# 32.net
KiCad netlist of a schematic drawn in Altium Designer
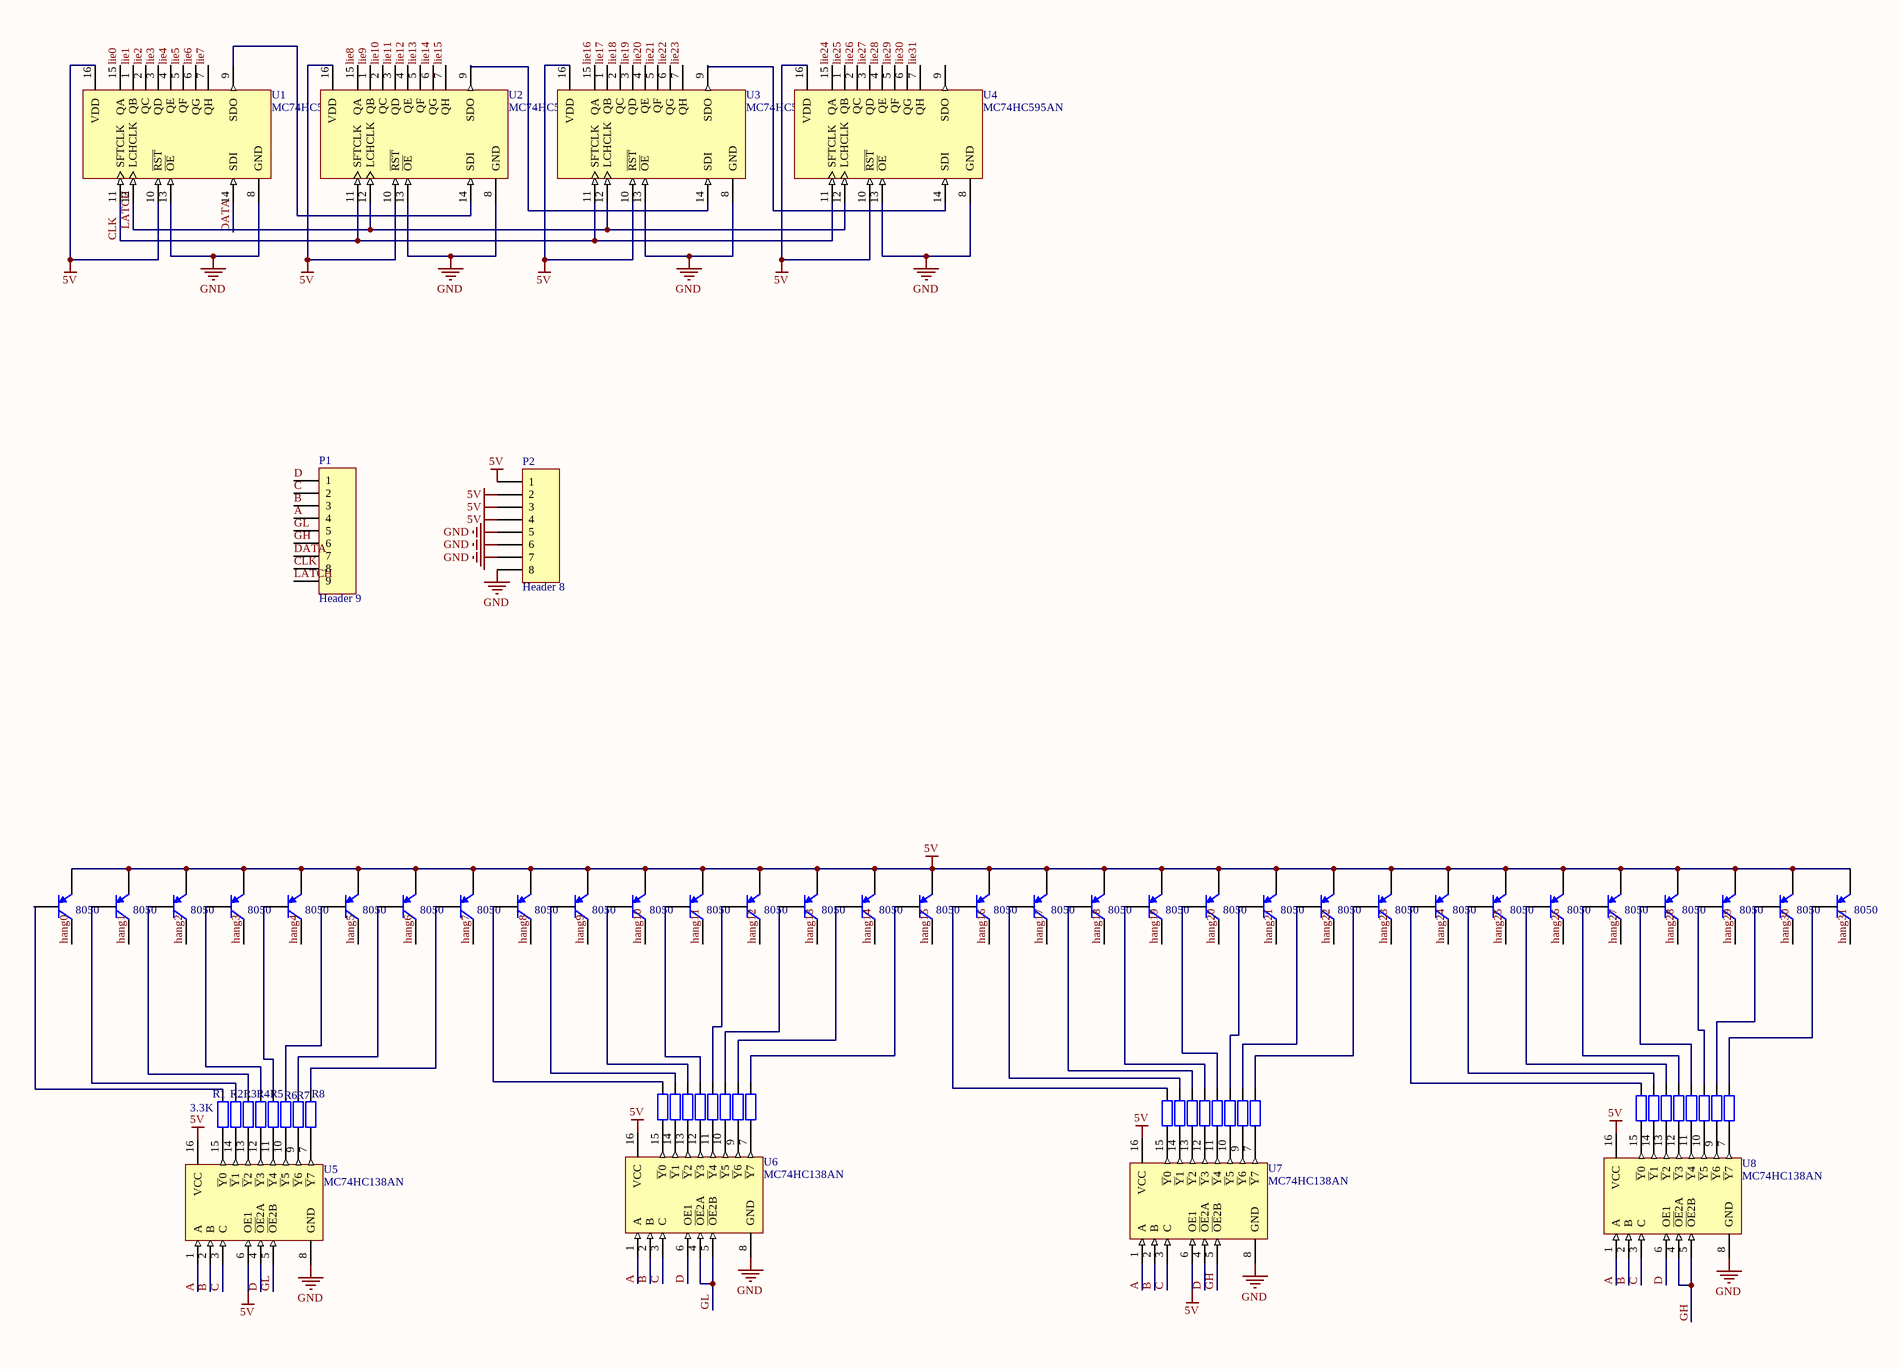
[diagram p0: 32点阵.SchDoc, left]
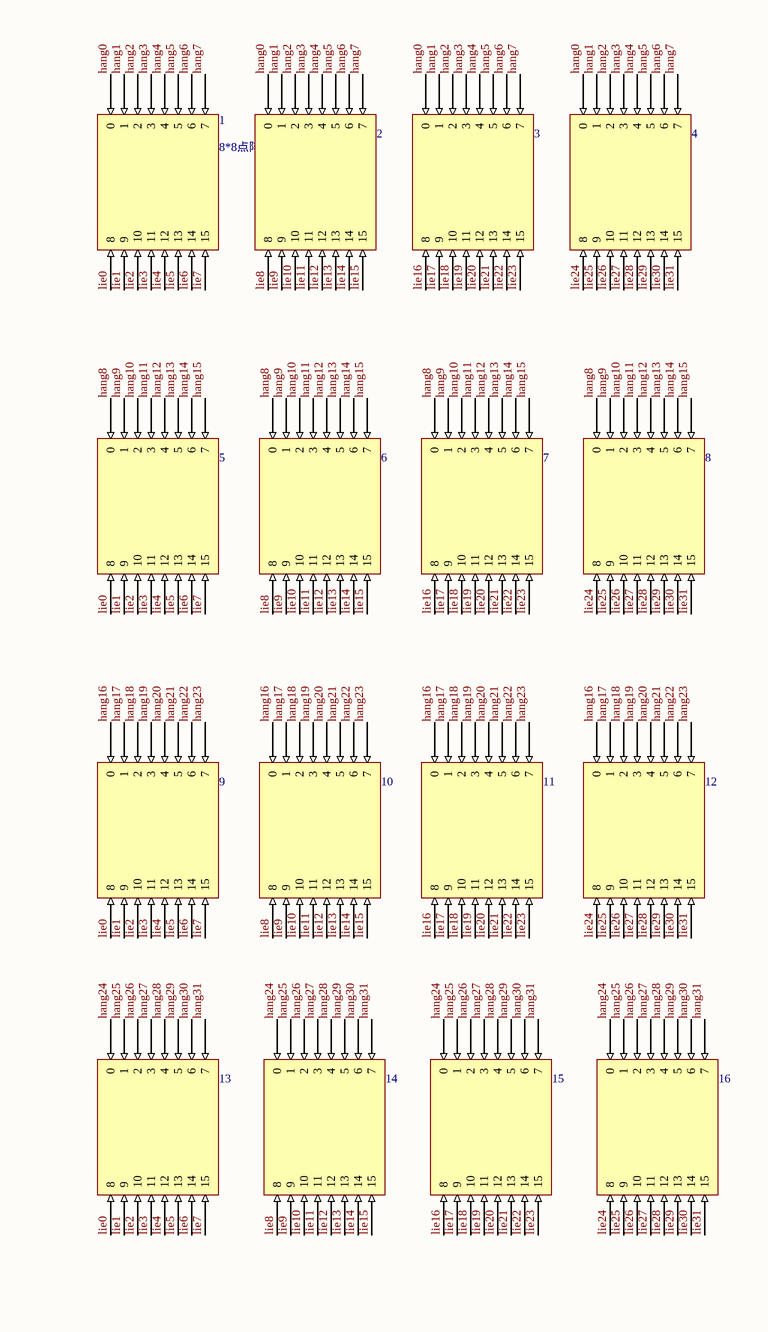
[diagram p1: 32点阵.SchDoc, right]

(export (version "E")
  (design (tool "Eeschema 10.0.6"))
  (components
    (comp (ref "1")
      (value "8乘8点阵")
      (footprint "32点阵:PCBComponent_1 - duplicate")
      (fields (field (name "8*8ΜÃÕÓ") "上面行，下面列"))
      (libsource (lib "88点阵") (part "8乘8点阵"))
    )
    (comp (ref "2")
      (value "8乘8点阵")
      (footprint "32点阵:PCBComponent_1 - duplicate")
      (libsource (lib "88点阵") (part "8乘8点阵"))
    )
    (comp (ref "3")
      (value "8乘8点阵")
      (footprint "32点阵:PCBComponent_1 - duplicate")
      (libsource (lib "88点阵") (part "8乘8点阵"))
    )
    (comp (ref "4")
      (value "8乘8点阵")
      (footprint "32点阵:PCBComponent_1 - duplicate")
      (libsource (lib "88点阵") (part "8乘8点阵"))
    )
    (comp (ref "5")
      (value "8乘8点阵")
      (footprint "32点阵:PCBComponent_1 - duplicate")
      (libsource (lib "88点阵") (part "8乘8点阵"))
    )
    (comp (ref "6")
      (value "8乘8点阵")
      (footprint "32点阵:PCBComponent_1 - duplicate")
      (libsource (lib "88点阵") (part "8乘8点阵"))
    )
    (comp (ref "7")
      (value "8乘8点阵")
      (footprint "32点阵:PCBComponent_1 - duplicate")
      (libsource (lib "88点阵") (part "8乘8点阵"))
    )
    (comp (ref "8")
      (value "8乘8点阵")
      (footprint "32点阵:PCBComponent_1 - duplicate")
      (libsource (lib "88点阵") (part "8乘8点阵"))
    )
    (comp (ref "9")
      (value "8乘8点阵")
      (footprint "32点阵:PCBComponent_1 - duplicate")
      (libsource (lib "88点阵") (part "8乘8点阵"))
    )
    (comp (ref "10")
      (value "8乘8点阵")
      (footprint "32点阵:PCBComponent_1 - duplicate")
      (libsource (lib "88点阵") (part "8乘8点阵"))
    )
    (comp (ref "11")
      (value "8乘8点阵")
      (footprint "32点阵:PCBComponent_1 - duplicate")
      (libsource (lib "88点阵") (part "8乘8点阵"))
    )
    (comp (ref "12")
      (value "8乘8点阵")
      (footprint "32点阵:PCBComponent_1 - duplicate")
      (libsource (lib "88点阵") (part "8乘8点阵"))
    )
    (comp (ref "13")
      (value "8乘8点阵")
      (footprint "32点阵:PCBComponent_1 - duplicate")
      (libsource (lib "88点阵") (part "8乘8点阵"))
    )
    (comp (ref "14")
      (value "8乘8点阵")
      (footprint "32点阵:PCBComponent_1 - duplicate")
      (libsource (lib "88点阵") (part "8乘8点阵"))
    )
    (comp (ref "15")
      (value "8乘8点阵")
      (footprint "32点阵:PCBComponent_1 - duplicate")
      (libsource (lib "88点阵") (part "8乘8点阵"))
    )
    (comp (ref "16")
      (value "8乘8点阵")
      (footprint "32点阵:PCBComponent_1 - duplicate")
      (libsource (lib "88点阵") (part "8乘8点阵"))
    )
    (comp (ref "P1")
      (value "Header 9")
      (footprint "HDR1X9")
      (description "Header, 9-Pin")
      (fields (field (name "PUBLISHER") "Altium Limited"))
      (libsource (lib "Miscellaneous Connectors") (part "Header 9"))
    )
    (comp (ref "P2")
      (value "Header 8")
      (footprint "HDR1X8")
      (description "Header, 8-Pin")
      (fields (field (name "PUBLISHER") "Altium Limited"))
      (libsource (lib "Miscellaneous Connectors") (part "Header 8"))
    )
    (comp (ref "Q1")
      (value "8050")
      (footprint "TO-92A")
      (description "PNP General Purpose Amplifier")
      (fields (field (name "PUBLISHER") "Altium Limited"))
      (libsource (lib "Miscellaneous Devices") (part "2N3906"))
    )
    (comp (ref "Q2")
      (value "8050")
      (footprint "TO-92A")
      (description "PNP General Purpose Amplifier")
      (fields (field (name "PUBLISHER") "Altium Limited"))
      (libsource (lib "Miscellaneous Devices") (part "2N3906"))
    )
    (comp (ref "Q3")
      (value "8050")
      (footprint "TO-92A")
      (description "PNP General Purpose Amplifier")
      (fields (field (name "PUBLISHER") "Altium Limited"))
      (libsource (lib "Miscellaneous Devices") (part "2N3906"))
    )
    (comp (ref "Q4")
      (value "8050")
      (footprint "TO-92A")
      (description "PNP General Purpose Amplifier")
      (fields (field (name "PUBLISHER") "Altium Limited"))
      (libsource (lib "Miscellaneous Devices") (part "2N3906"))
    )
    (comp (ref "Q5")
      (value "8050")
      (footprint "TO-92A")
      (description "PNP General Purpose Amplifier")
      (fields (field (name "PUBLISHER") "Altium Limited"))
      (libsource (lib "Miscellaneous Devices") (part "2N3906"))
    )
    (comp (ref "Q6")
      (value "8050")
      (footprint "TO-92A")
      (description "PNP General Purpose Amplifier")
      (fields (field (name "PUBLISHER") "Altium Limited"))
      (libsource (lib "Miscellaneous Devices") (part "2N3906"))
    )
    (comp (ref "Q7")
      (value "8050")
      (footprint "TO-92A")
      (description "PNP General Purpose Amplifier")
      (fields (field (name "PUBLISHER") "Altium Limited"))
      (libsource (lib "Miscellaneous Devices") (part "2N3906"))
    )
    (comp (ref "Q8")
      (value "8050")
      (footprint "TO-92A")
      (description "PNP General Purpose Amplifier")
      (fields (field (name "PUBLISHER") "Altium Limited"))
      (libsource (lib "Miscellaneous Devices") (part "2N3906"))
    )
    (comp (ref "Q9")
      (value "8050")
      (footprint "TO-92A")
      (description "PNP General Purpose Amplifier")
      (fields (field (name "PUBLISHER") "Altium Limited"))
      (libsource (lib "Miscellaneous Devices") (part "2N3906"))
    )
    (comp (ref "Q10")
      (value "8050")
      (footprint "TO-92A")
      (description "PNP General Purpose Amplifier")
      (fields (field (name "PUBLISHER") "Altium Limited"))
      (libsource (lib "Miscellaneous Devices") (part "2N3906"))
    )
    (comp (ref "Q11")
      (value "8050")
      (footprint "TO-92A")
      (description "PNP General Purpose Amplifier")
      (fields (field (name "PUBLISHER") "Altium Limited"))
      (libsource (lib "Miscellaneous Devices") (part "2N3906"))
    )
    (comp (ref "Q12")
      (value "8050")
      (footprint "TO-92A")
      (description "PNP General Purpose Amplifier")
      (fields (field (name "PUBLISHER") "Altium Limited"))
      (libsource (lib "Miscellaneous Devices") (part "2N3906"))
    )
    (comp (ref "Q13")
      (value "8050")
      (footprint "TO-92A")
      (description "PNP General Purpose Amplifier")
      (fields (field (name "PUBLISHER") "Altium Limited"))
      (libsource (lib "Miscellaneous Devices") (part "2N3906"))
    )
    (comp (ref "Q14")
      (value "8050")
      (footprint "TO-92A")
      (description "PNP General Purpose Amplifier")
      (fields (field (name "PUBLISHER") "Altium Limited"))
      (libsource (lib "Miscellaneous Devices") (part "2N3906"))
    )
    (comp (ref "Q15")
      (value "8050")
      (footprint "TO-92A")
      (description "PNP General Purpose Amplifier")
      (fields (field (name "PUBLISHER") "Altium Limited"))
      (libsource (lib "Miscellaneous Devices") (part "2N3906"))
    )
    (comp (ref "Q16")
      (value "8050")
      (footprint "TO-92A")
      (description "PNP General Purpose Amplifier")
      (fields (field (name "PUBLISHER") "Altium Limited"))
      (libsource (lib "Miscellaneous Devices") (part "2N3906"))
    )
    (comp (ref "Q17")
      (value "8050")
      (footprint "TO-92A")
      (description "PNP General Purpose Amplifier")
      (fields (field (name "PUBLISHER") "Altium Limited"))
      (libsource (lib "Miscellaneous Devices") (part "2N3906"))
    )
    (comp (ref "Q18")
      (value "8050")
      (footprint "TO-92A")
      (description "PNP General Purpose Amplifier")
      (fields (field (name "PUBLISHER") "Altium Limited"))
      (libsource (lib "Miscellaneous Devices") (part "2N3906"))
    )
    (comp (ref "Q19")
      (value "8050")
      (footprint "TO-92A")
      (description "PNP General Purpose Amplifier")
      (fields (field (name "PUBLISHER") "Altium Limited"))
      (libsource (lib "Miscellaneous Devices") (part "2N3906"))
    )
    (comp (ref "Q20")
      (value "8050")
      (footprint "TO-92A")
      (description "PNP General Purpose Amplifier")
      (fields (field (name "PUBLISHER") "Altium Limited"))
      (libsource (lib "Miscellaneous Devices") (part "2N3906"))
    )
    (comp (ref "Q21")
      (value "8050")
      (footprint "TO-92A")
      (description "PNP General Purpose Amplifier")
      (fields (field (name "PUBLISHER") "Altium Limited"))
      (libsource (lib "Miscellaneous Devices") (part "2N3906"))
    )
    (comp (ref "Q22")
      (value "8050")
      (footprint "TO-92A")
      (description "PNP General Purpose Amplifier")
      (fields (field (name "PUBLISHER") "Altium Limited"))
      (libsource (lib "Miscellaneous Devices") (part "2N3906"))
    )
    (comp (ref "Q23")
      (value "8050")
      (footprint "TO-92A")
      (description "PNP General Purpose Amplifier")
      (fields (field (name "PUBLISHER") "Altium Limited"))
      (libsource (lib "Miscellaneous Devices") (part "2N3906"))
    )
    (comp (ref "Q24")
      (value "8050")
      (footprint "TO-92A")
      (description "PNP General Purpose Amplifier")
      (fields (field (name "PUBLISHER") "Altium Limited"))
      (libsource (lib "Miscellaneous Devices") (part "2N3906"))
    )
    (comp (ref "Q25")
      (value "8050")
      (footprint "TO-92A")
      (description "PNP General Purpose Amplifier")
      (fields (field (name "PUBLISHER") "Altium Limited"))
      (libsource (lib "Miscellaneous Devices") (part "2N3906"))
    )
    (comp (ref "Q26")
      (value "8050")
      (footprint "TO-92A")
      (description "PNP General Purpose Amplifier")
      (fields (field (name "PUBLISHER") "Altium Limited"))
      (libsource (lib "Miscellaneous Devices") (part "2N3906"))
    )
    (comp (ref "Q27")
      (value "8050")
      (footprint "TO-92A")
      (description "PNP General Purpose Amplifier")
      (fields (field (name "PUBLISHER") "Altium Limited"))
      (libsource (lib "Miscellaneous Devices") (part "2N3906"))
    )
    (comp (ref "Q28")
      (value "8050")
      (footprint "TO-92A")
      (description "PNP General Purpose Amplifier")
      (fields (field (name "PUBLISHER") "Altium Limited"))
      (libsource (lib "Miscellaneous Devices") (part "2N3906"))
    )
    (comp (ref "Q29")
      (value "8050")
      (footprint "TO-92A")
      (description "PNP General Purpose Amplifier")
      (fields (field (name "PUBLISHER") "Altium Limited"))
      (libsource (lib "Miscellaneous Devices") (part "2N3906"))
    )
    (comp (ref "Q30")
      (value "8050")
      (footprint "TO-92A")
      (description "PNP General Purpose Amplifier")
      (fields (field (name "PUBLISHER") "Altium Limited"))
      (libsource (lib "Miscellaneous Devices") (part "2N3906"))
    )
    (comp (ref "Q31")
      (value "8050")
      (footprint "TO-92A")
      (description "PNP General Purpose Amplifier")
      (fields (field (name "PUBLISHER") "Altium Limited"))
      (libsource (lib "Miscellaneous Devices") (part "2N3906"))
    )
    (comp (ref "Q32")
      (value "8050")
      (footprint "TO-92A")
      (description "PNP General Purpose Amplifier")
      (fields (field (name "PUBLISHER") "Altium Limited"))
      (libsource (lib "Miscellaneous Devices") (part "2N3906"))
    )
    (comp (ref "R1")
      (value "3.3K")
      (footprint "AXIAL-0.4")
      (description "Resistor")
      (fields (field (name "Comment") "Res2") (field (name "PUBLISHER") "Altium Limited"))
      (libsource (lib "Miscellaneous Devices") (part "Res2"))
    )
    (comp (ref "R2")
      (value "Res2")
      (footprint "AXIAL-0.4")
      (description "Resistor")
      (fields (field (name "PUBLISHER") "Altium Limited"))
      (libsource (lib "Miscellaneous Devices") (part "Res2"))
    )
    (comp (ref "R3")
      (value "Res2")
      (footprint "AXIAL-0.4")
      (description "Resistor")
      (fields (field (name "PUBLISHER") "Altium Limited"))
      (libsource (lib "Miscellaneous Devices") (part "Res2"))
    )
    (comp (ref "R4")
      (value "Res2")
      (footprint "AXIAL-0.4")
      (description "Resistor")
      (fields (field (name "PUBLISHER") "Altium Limited"))
      (libsource (lib "Miscellaneous Devices") (part "Res2"))
    )
    (comp (ref "R5")
      (value "Res2")
      (footprint "AXIAL-0.4")
      (description "Resistor")
      (fields (field (name "PUBLISHER") "Altium Limited"))
      (libsource (lib "Miscellaneous Devices") (part "Res2"))
    )
    (comp (ref "R6")
      (value "Res2")
      (footprint "AXIAL-0.4")
      (description "Resistor")
      (fields (field (name "PUBLISHER") "Altium Limited"))
      (libsource (lib "Miscellaneous Devices") (part "Res2"))
    )
    (comp (ref "R7")
      (value "Res2")
      (footprint "AXIAL-0.4")
      (description "Resistor")
      (fields (field (name "PUBLISHER") "Altium Limited"))
      (libsource (lib "Miscellaneous Devices") (part "Res2"))
    )
    (comp (ref "R8")
      (value "Res2")
      (footprint "AXIAL-0.4")
      (description "Resistor")
      (fields (field (name "PUBLISHER") "Altium Limited"))
      (libsource (lib "Miscellaneous Devices") (part "Res2"))
    )
    (comp (ref "R9")
      (value "Res2")
      (footprint "AXIAL-0.4")
      (description "Resistor")
      (fields (field (name "PUBLISHER") "Altium Limited"))
      (libsource (lib "Miscellaneous Devices") (part "Res2"))
    )
    (comp (ref "R10")
      (value "Res2")
      (footprint "AXIAL-0.4")
      (description "Resistor")
      (fields (field (name "PUBLISHER") "Altium Limited"))
      (libsource (lib "Miscellaneous Devices") (part "Res2"))
    )
    (comp (ref "R11")
      (value "Res2")
      (footprint "AXIAL-0.4")
      (description "Resistor")
      (fields (field (name "PUBLISHER") "Altium Limited"))
      (libsource (lib "Miscellaneous Devices") (part "Res2"))
    )
    (comp (ref "R12")
      (value "Res2")
      (footprint "AXIAL-0.4")
      (description "Resistor")
      (fields (field (name "PUBLISHER") "Altium Limited"))
      (libsource (lib "Miscellaneous Devices") (part "Res2"))
    )
    (comp (ref "R13")
      (value "Res2")
      (footprint "AXIAL-0.4")
      (description "Resistor")
      (fields (field (name "PUBLISHER") "Altium Limited"))
      (libsource (lib "Miscellaneous Devices") (part "Res2"))
    )
    (comp (ref "R14")
      (value "Res2")
      (footprint "AXIAL-0.4")
      (description "Resistor")
      (fields (field (name "PUBLISHER") "Altium Limited"))
      (libsource (lib "Miscellaneous Devices") (part "Res2"))
    )
    (comp (ref "R15")
      (value "Res2")
      (footprint "AXIAL-0.4")
      (description "Resistor")
      (fields (field (name "PUBLISHER") "Altium Limited"))
      (libsource (lib "Miscellaneous Devices") (part "Res2"))
    )
    (comp (ref "R16")
      (value "Res2")
      (footprint "AXIAL-0.4")
      (description "Resistor")
      (fields (field (name "PUBLISHER") "Altium Limited"))
      (libsource (lib "Miscellaneous Devices") (part "Res2"))
    )
    (comp (ref "R17")
      (value "Res2")
      (footprint "AXIAL-0.4")
      (description "Resistor")
      (fields (field (name "PUBLISHER") "Altium Limited"))
      (libsource (lib "Miscellaneous Devices") (part "Res2"))
    )
    (comp (ref "R18")
      (value "Res2")
      (footprint "AXIAL-0.4")
      (description "Resistor")
      (fields (field (name "PUBLISHER") "Altium Limited"))
      (libsource (lib "Miscellaneous Devices") (part "Res2"))
    )
    (comp (ref "R19")
      (value "Res2")
      (footprint "AXIAL-0.4")
      (description "Resistor")
      (fields (field (name "PUBLISHER") "Altium Limited"))
      (libsource (lib "Miscellaneous Devices") (part "Res2"))
    )
    (comp (ref "R20")
      (value "Res2")
      (footprint "AXIAL-0.4")
      (description "Resistor")
      (fields (field (name "PUBLISHER") "Altium Limited"))
      (libsource (lib "Miscellaneous Devices") (part "Res2"))
    )
    (comp (ref "R21")
      (value "Res2")
      (footprint "AXIAL-0.4")
      (description "Resistor")
      (fields (field (name "PUBLISHER") "Altium Limited"))
      (libsource (lib "Miscellaneous Devices") (part "Res2"))
    )
    (comp (ref "R22")
      (value "Res2")
      (footprint "AXIAL-0.4")
      (description "Resistor")
      (fields (field (name "PUBLISHER") "Altium Limited"))
      (libsource (lib "Miscellaneous Devices") (part "Res2"))
    )
    (comp (ref "R23")
      (value "Res2")
      (footprint "AXIAL-0.4")
      (description "Resistor")
      (fields (field (name "PUBLISHER") "Altium Limited"))
      (libsource (lib "Miscellaneous Devices") (part "Res2"))
    )
    (comp (ref "R24")
      (value "Res2")
      (footprint "AXIAL-0.4")
      (description "Resistor")
      (fields (field (name "PUBLISHER") "Altium Limited"))
      (libsource (lib "Miscellaneous Devices") (part "Res2"))
    )
    (comp (ref "R25")
      (value "Res2")
      (footprint "AXIAL-0.4")
      (description "Resistor")
      (fields (field (name "PUBLISHER") "Altium Limited"))
      (libsource (lib "Miscellaneous Devices") (part "Res2"))
    )
    (comp (ref "R26")
      (value "Res2")
      (footprint "AXIAL-0.4")
      (description "Resistor")
      (fields (field (name "PUBLISHER") "Altium Limited"))
      (libsource (lib "Miscellaneous Devices") (part "Res2"))
    )
    (comp (ref "R27")
      (value "Res2")
      (footprint "AXIAL-0.4")
      (description "Resistor")
      (fields (field (name "PUBLISHER") "Altium Limited"))
      (libsource (lib "Miscellaneous Devices") (part "Res2"))
    )
    (comp (ref "R28")
      (value "Res2")
      (footprint "AXIAL-0.4")
      (description "Resistor")
      (fields (field (name "PUBLISHER") "Altium Limited"))
      (libsource (lib "Miscellaneous Devices") (part "Res2"))
    )
    (comp (ref "R29")
      (value "Res2")
      (footprint "AXIAL-0.4")
      (description "Resistor")
      (fields (field (name "PUBLISHER") "Altium Limited"))
      (libsource (lib "Miscellaneous Devices") (part "Res2"))
    )
    (comp (ref "R30")
      (value "Res2")
      (footprint "AXIAL-0.4")
      (description "Resistor")
      (fields (field (name "PUBLISHER") "Altium Limited"))
      (libsource (lib "Miscellaneous Devices") (part "Res2"))
    )
    (comp (ref "R31")
      (value "Res2")
      (footprint "AXIAL-0.4")
      (description "Resistor")
      (fields (field (name "PUBLISHER") "Altium Limited"))
      (libsource (lib "Miscellaneous Devices") (part "Res2"))
    )
    (comp (ref "R32")
      (value "Res2")
      (footprint "AXIAL-0.4")
      (description "Resistor")
      (fields (field (name "PUBLISHER") "Altium Limited"))
      (libsource (lib "Miscellaneous Devices") (part "Res2"))
    )
    (comp (ref "U1")
      (value "MC74HC595AN")
      (footprint "648-08")
      (description "8-Bit Serial-Input/Serial or Prallel-Output Shift Register with Latched 3-State Outputs")
      (fields (field (name "PUBLISHER") "Altium Limited"))
      (libsource (lib "ON Semi Logic Register") (part "MC74HC595AN"))
    )
    (comp (ref "U2")
      (value "MC74HC595AN")
      (footprint "648-08")
      (description "8-Bit Serial-Input/Serial or Prallel-Output Shift Register with Latched 3-State Outputs")
      (fields (field (name "PUBLISHER") "Altium Limited"))
      (libsource (lib "ON Semi Logic Register") (part "MC74HC595AN"))
    )
    (comp (ref "U3")
      (value "MC74HC595AN")
      (footprint "648-08")
      (description "8-Bit Serial-Input/Serial or Prallel-Output Shift Register with Latched 3-State Outputs")
      (fields (field (name "PUBLISHER") "Altium Limited"))
      (libsource (lib "ON Semi Logic Register") (part "MC74HC595AN"))
    )
    (comp (ref "U4")
      (value "MC74HC595AN")
      (footprint "648-08")
      (description "8-Bit Serial-Input/Serial or Prallel-Output Shift Register with Latched 3-State Outputs")
      (fields (field (name "PUBLISHER") "Altium Limited"))
      (libsource (lib "ON Semi Logic Register") (part "MC74HC595AN"))
    )
    (comp (ref "U5")
      (value "MC74HC138AN")
      (footprint "648-08")
      (description "1-of-8 Decoder/Demultiplexer")
      (fields (field (name "PUBLISHER") "Altium Limited"))
      (libsource (lib "ON Semi Logic Decoder Demux") (part "MC74HC138AN"))
    )
    (comp (ref "U6")
      (value "MC74HC138AN")
      (footprint "648-08")
      (description "1-of-8 Decoder/Demultiplexer")
      (fields (field (name "PUBLISHER") "Altium Limited"))
      (libsource (lib "ON Semi Logic Decoder Demux") (part "MC74HC138AN"))
    )
    (comp (ref "U7")
      (value "MC74HC138AN")
      (footprint "648-08")
      (description "1-of-8 Decoder/Demultiplexer")
      (fields (field (name "PUBLISHER") "Altium Limited"))
      (libsource (lib "ON Semi Logic Decoder Demux") (part "MC74HC138AN"))
    )
    (comp (ref "U8")
      (value "MC74HC138AN")
      (footprint "648-08")
      (description "1-of-8 Decoder/Demultiplexer")
      (fields (field (name "PUBLISHER") "Altium Limited"))
      (libsource (lib "ON Semi Logic Decoder Demux") (part "MC74HC138AN"))
    )
  )
  (nets
    (net (code "1") (name "/A") (class "Default")
      (node (ref "P1") (pin "4") (pinfunction "4_4") (pintype "passive"))
      (node (ref "U5") (pin "1") (pinfunction "A_1") (pintype "input"))
      (node (ref "U6") (pin "1") (pinfunction "A_1") (pintype "input"))
      (node (ref "U7") (pin "1") (pinfunction "A_1") (pintype "input"))
      (node (ref "U8") (pin "1") (pinfunction "A_1") (pintype "input"))
    )
    (net (code "2") (name "/B") (class "Default")
      (node (ref "P1") (pin "3") (pinfunction "3_3") (pintype "passive"))
      (node (ref "U5") (pin "2") (pinfunction "B_2") (pintype "input"))
      (node (ref "U6") (pin "2") (pinfunction "B_2") (pintype "input"))
      (node (ref "U7") (pin "2") (pinfunction "B_2") (pintype "input"))
      (node (ref "U8") (pin "2") (pinfunction "B_2") (pintype "input"))
    )
    (net (code "3") (name "/C") (class "Default")
      (node (ref "P1") (pin "2") (pinfunction "2_2") (pintype "passive"))
      (node (ref "U5") (pin "3") (pinfunction "C_3") (pintype "input"))
      (node (ref "U6") (pin "3") (pinfunction "C_3") (pintype "input"))
      (node (ref "U7") (pin "3") (pinfunction "C_3") (pintype "input"))
      (node (ref "U8") (pin "3") (pinfunction "C_3") (pintype "input"))
    )
    (net (code "4") (name "/CLK") (class "Default")
      (node (ref "P1") (pin "8") (pinfunction "8_8") (pintype "passive"))
      (node (ref "U1") (pin "11") (pinfunction "SFTCLK_11") (pintype "input"))
      (node (ref "U2") (pin "11") (pinfunction "SFTCLK_11") (pintype "input"))
      (node (ref "U3") (pin "11") (pinfunction "SFTCLK_11") (pintype "input"))
      (node (ref "U4") (pin "11") (pinfunction "SFTCLK_11") (pintype "input"))
    )
    (net (code "5") (name "/D") (class "Default")
      (node (ref "P1") (pin "1") (pinfunction "1_1") (pintype "passive"))
      (node (ref "U5") (pin "4") (pinfunction "~{OE}2A_4") (pintype "input"))
      (node (ref "U6") (pin "6") (pinfunction "OE1_6") (pintype "input"))
      (node (ref "U7") (pin "4") (pinfunction "~{OE}2A_4") (pintype "input"))
      (node (ref "U8") (pin "6") (pinfunction "OE1_6") (pintype "input"))
    )
    (net (code "6") (name "/DATA") (class "Default")
      (node (ref "P1") (pin "7") (pinfunction "7_7") (pintype "passive"))
      (node (ref "U1") (pin "14") (pinfunction "SDI_14") (pintype "input"))
    )
    (net (code "7") (name "/GH") (class "Default")
      (node (ref "P1") (pin "6") (pinfunction "6_6") (pintype "passive"))
      (node (ref "U7") (pin "5") (pinfunction "~{OE}2B_5") (pintype "input"))
      (node (ref "U8") (pin "4") (pinfunction "~{OE}2A_4") (pintype "input"))
      (node (ref "U8") (pin "5") (pinfunction "~{OE}2B_5") (pintype "input"))
    )
    (net (code "8") (name "/GL") (class "Default")
      (node (ref "P1") (pin "5") (pinfunction "5_5") (pintype "passive"))
      (node (ref "U5") (pin "5") (pinfunction "~{OE}2B_5") (pintype "input"))
      (node (ref "U6") (pin "4") (pinfunction "~{OE}2A_4") (pintype "input"))
      (node (ref "U6") (pin "5") (pinfunction "~{OE}2B_5") (pintype "input"))
    )
    (net (code "9") (name "/LATCH") (class "Default")
      (node (ref "P1") (pin "9") (pinfunction "9_9") (pintype "passive"))
      (node (ref "U1") (pin "12") (pinfunction "LCHCLK_12") (pintype "input"))
      (node (ref "U2") (pin "12") (pinfunction "LCHCLK_12") (pintype "input"))
      (node (ref "U3") (pin "12") (pinfunction "LCHCLK_12") (pintype "input"))
      (node (ref "U4") (pin "12") (pinfunction "LCHCLK_12") (pintype "input"))
    )
    (net (code "10") (name "/hang0") (class "Default")
      (node (ref "1") (pin "0") (pinfunction "0_0") (pintype "input"))
      (node (ref "2") (pin "0") (pinfunction "0_0") (pintype "input"))
      (node (ref "3") (pin "0") (pinfunction "0_0") (pintype "input"))
      (node (ref "4") (pin "0") (pinfunction "0_0") (pintype "input"))
      (node (ref "Q1") (pin "3") (pinfunction "C_3") (pintype "passive"))
    )
    (net (code "11") (name "/hang1") (class "Default")
      (node (ref "1") (pin "1") (pinfunction "1_1") (pintype "input"))
      (node (ref "2") (pin "1") (pinfunction "1_1") (pintype "input"))
      (node (ref "3") (pin "1") (pinfunction "1_1") (pintype "input"))
      (node (ref "4") (pin "1") (pinfunction "1_1") (pintype "input"))
      (node (ref "Q2") (pin "3") (pinfunction "C_3") (pintype "passive"))
    )
    (net (code "12") (name "/hang2") (class "Default")
      (node (ref "1") (pin "2") (pinfunction "2_2") (pintype "input"))
      (node (ref "2") (pin "2") (pinfunction "2_2") (pintype "input"))
      (node (ref "3") (pin "2") (pinfunction "2_2") (pintype "input"))
      (node (ref "4") (pin "2") (pinfunction "2_2") (pintype "input"))
      (node (ref "Q3") (pin "3") (pinfunction "C_3") (pintype "passive"))
    )
    (net (code "13") (name "/hang3") (class "Default")
      (node (ref "1") (pin "3") (pinfunction "3_3") (pintype "input"))
      (node (ref "2") (pin "3") (pinfunction "3_3") (pintype "input"))
      (node (ref "3") (pin "3") (pinfunction "3_3") (pintype "input"))
      (node (ref "4") (pin "3") (pinfunction "3_3") (pintype "input"))
      (node (ref "Q4") (pin "3") (pinfunction "C_3") (pintype "passive"))
    )
    (net (code "14") (name "/hang4") (class "Default")
      (node (ref "1") (pin "4") (pinfunction "4_4") (pintype "input"))
      (node (ref "2") (pin "4") (pinfunction "4_4") (pintype "input"))
      (node (ref "3") (pin "4") (pinfunction "4_4") (pintype "input"))
      (node (ref "4") (pin "4") (pinfunction "4_4") (pintype "input"))
      (node (ref "Q5") (pin "3") (pinfunction "C_3") (pintype "passive"))
    )
    (net (code "15") (name "/hang5") (class "Default")
      (node (ref "1") (pin "5") (pinfunction "5_5") (pintype "input"))
      (node (ref "2") (pin "5") (pinfunction "5_5") (pintype "input"))
      (node (ref "3") (pin "5") (pinfunction "5_5") (pintype "input"))
      (node (ref "4") (pin "5") (pinfunction "5_5") (pintype "input"))
      (node (ref "Q6") (pin "3") (pinfunction "C_3") (pintype "passive"))
    )
    (net (code "16") (name "/hang6") (class "Default")
      (node (ref "1") (pin "6") (pinfunction "6_6") (pintype "input"))
      (node (ref "2") (pin "6") (pinfunction "6_6") (pintype "input"))
      (node (ref "3") (pin "6") (pinfunction "6_6") (pintype "input"))
      (node (ref "4") (pin "6") (pinfunction "6_6") (pintype "input"))
      (node (ref "Q7") (pin "3") (pinfunction "C_3") (pintype "passive"))
    )
    (net (code "17") (name "/hang7") (class "Default")
      (node (ref "1") (pin "7") (pinfunction "7_7") (pintype "input"))
      (node (ref "2") (pin "7") (pinfunction "7_7") (pintype "input"))
      (node (ref "3") (pin "7") (pinfunction "7_7") (pintype "input"))
      (node (ref "4") (pin "7") (pinfunction "7_7") (pintype "input"))
      (node (ref "Q8") (pin "3") (pinfunction "C_3") (pintype "passive"))
    )
    (net (code "18") (name "/hang8") (class "Default")
      (node (ref "5") (pin "0") (pinfunction "0_0") (pintype "input"))
      (node (ref "6") (pin "0") (pinfunction "0_0") (pintype "input"))
      (node (ref "7") (pin "0") (pinfunction "0_0") (pintype "input"))
      (node (ref "8") (pin "0") (pinfunction "0_0") (pintype "input"))
      (node (ref "Q9") (pin "3") (pinfunction "C_3") (pintype "passive"))
    )
    (net (code "19") (name "/hang9") (class "Default")
      (node (ref "5") (pin "1") (pinfunction "1_1") (pintype "input"))
      (node (ref "6") (pin "1") (pinfunction "1_1") (pintype "input"))
      (node (ref "7") (pin "1") (pinfunction "1_1") (pintype "input"))
      (node (ref "8") (pin "1") (pinfunction "1_1") (pintype "input"))
      (node (ref "Q10") (pin "3") (pinfunction "C_3") (pintype "passive"))
    )
    (net (code "20") (name "/hang10") (class "Default")
      (node (ref "5") (pin "2") (pinfunction "2_2") (pintype "input"))
      (node (ref "6") (pin "2") (pinfunction "2_2") (pintype "input"))
      (node (ref "7") (pin "2") (pinfunction "2_2") (pintype "input"))
      (node (ref "8") (pin "2") (pinfunction "2_2") (pintype "input"))
      (node (ref "Q11") (pin "3") (pinfunction "C_3") (pintype "passive"))
    )
    (net (code "21") (name "/hang11") (class "Default")
      (node (ref "5") (pin "3") (pinfunction "3_3") (pintype "input"))
      (node (ref "6") (pin "3") (pinfunction "3_3") (pintype "input"))
      (node (ref "7") (pin "3") (pinfunction "3_3") (pintype "input"))
      (node (ref "8") (pin "3") (pinfunction "3_3") (pintype "input"))
      (node (ref "Q12") (pin "3") (pinfunction "C_3") (pintype "passive"))
    )
    (net (code "22") (name "/hang12") (class "Default")
      (node (ref "5") (pin "4") (pinfunction "4_4") (pintype "input"))
      (node (ref "6") (pin "4") (pinfunction "4_4") (pintype "input"))
      (node (ref "7") (pin "4") (pinfunction "4_4") (pintype "input"))
      (node (ref "8") (pin "4") (pinfunction "4_4") (pintype "input"))
      (node (ref "Q13") (pin "3") (pinfunction "C_3") (pintype "passive"))
    )
    (net (code "23") (name "/hang13") (class "Default")
      (node (ref "5") (pin "5") (pinfunction "5_5") (pintype "input"))
      (node (ref "6") (pin "5") (pinfunction "5_5") (pintype "input"))
      (node (ref "7") (pin "5") (pinfunction "5_5") (pintype "input"))
      (node (ref "8") (pin "5") (pinfunction "5_5") (pintype "input"))
      (node (ref "Q14") (pin "3") (pinfunction "C_3") (pintype "passive"))
    )
    (net (code "24") (name "/hang14") (class "Default")
      (node (ref "5") (pin "6") (pinfunction "6_6") (pintype "input"))
      (node (ref "6") (pin "6") (pinfunction "6_6") (pintype "input"))
      (node (ref "7") (pin "6") (pinfunction "6_6") (pintype "input"))
      (node (ref "8") (pin "6") (pinfunction "6_6") (pintype "input"))
      (node (ref "Q15") (pin "3") (pinfunction "C_3") (pintype "passive"))
    )
    (net (code "25") (name "/hang15") (class "Default")
      (node (ref "5") (pin "7") (pinfunction "7_7") (pintype "input"))
      (node (ref "6") (pin "7") (pinfunction "7_7") (pintype "input"))
      (node (ref "7") (pin "7") (pinfunction "7_7") (pintype "input"))
      (node (ref "8") (pin "7") (pinfunction "7_7") (pintype "input"))
      (node (ref "Q16") (pin "3") (pinfunction "C_3") (pintype "passive"))
    )
    (net (code "26") (name "/hang16") (class "Default")
      (node (ref "10") (pin "0") (pinfunction "0_0") (pintype "input"))
      (node (ref "11") (pin "0") (pinfunction "0_0") (pintype "input"))
      (node (ref "12") (pin "0") (pinfunction "0_0") (pintype "input"))
      (node (ref "9") (pin "0") (pinfunction "0_0") (pintype "input"))
      (node (ref "Q17") (pin "3") (pinfunction "C_3") (pintype "passive"))
    )
    (net (code "27") (name "/hang17") (class "Default")
      (node (ref "10") (pin "1") (pinfunction "1_1") (pintype "input"))
      (node (ref "11") (pin "1") (pinfunction "1_1") (pintype "input"))
      (node (ref "12") (pin "1") (pinfunction "1_1") (pintype "input"))
      (node (ref "9") (pin "1") (pinfunction "1_1") (pintype "input"))
      (node (ref "Q18") (pin "3") (pinfunction "C_3") (pintype "passive"))
    )
    (net (code "28") (name "/hang18") (class "Default")
      (node (ref "10") (pin "2") (pinfunction "2_2") (pintype "input"))
      (node (ref "11") (pin "2") (pinfunction "2_2") (pintype "input"))
      (node (ref "12") (pin "2") (pinfunction "2_2") (pintype "input"))
      (node (ref "9") (pin "2") (pinfunction "2_2") (pintype "input"))
      (node (ref "Q19") (pin "3") (pinfunction "C_3") (pintype "passive"))
    )
    (net (code "29") (name "/hang19") (class "Default")
      (node (ref "10") (pin "3") (pinfunction "3_3") (pintype "input"))
      (node (ref "11") (pin "3") (pinfunction "3_3") (pintype "input"))
      (node (ref "12") (pin "3") (pinfunction "3_3") (pintype "input"))
      (node (ref "9") (pin "3") (pinfunction "3_3") (pintype "input"))
      (node (ref "Q20") (pin "3") (pinfunction "C_3") (pintype "passive"))
    )
    (net (code "30") (name "/hang20") (class "Default")
      (node (ref "10") (pin "4") (pinfunction "4_4") (pintype "input"))
      (node (ref "11") (pin "4") (pinfunction "4_4") (pintype "input"))
      (node (ref "12") (pin "4") (pinfunction "4_4") (pintype "input"))
      (node (ref "9") (pin "4") (pinfunction "4_4") (pintype "input"))
      (node (ref "Q21") (pin "3") (pinfunction "C_3") (pintype "passive"))
    )
    (net (code "31") (name "/hang21") (class "Default")
      (node (ref "10") (pin "5") (pinfunction "5_5") (pintype "input"))
      (node (ref "11") (pin "5") (pinfunction "5_5") (pintype "input"))
      (node (ref "12") (pin "5") (pinfunction "5_5") (pintype "input"))
      (node (ref "9") (pin "5") (pinfunction "5_5") (pintype "input"))
      (node (ref "Q22") (pin "3") (pinfunction "C_3") (pintype "passive"))
    )
    (net (code "32") (name "/hang22") (class "Default")
      (node (ref "10") (pin "6") (pinfunction "6_6") (pintype "input"))
      (node (ref "11") (pin "6") (pinfunction "6_6") (pintype "input"))
      (node (ref "12") (pin "6") (pinfunction "6_6") (pintype "input"))
      (node (ref "9") (pin "6") (pinfunction "6_6") (pintype "input"))
      (node (ref "Q23") (pin "3") (pinfunction "C_3") (pintype "passive"))
    )
    (net (code "33") (name "/hang23") (class "Default")
      (node (ref "10") (pin "7") (pinfunction "7_7") (pintype "input"))
      (node (ref "11") (pin "7") (pinfunction "7_7") (pintype "input"))
      (node (ref "12") (pin "7") (pinfunction "7_7") (pintype "input"))
      (node (ref "9") (pin "7") (pinfunction "7_7") (pintype "input"))
      (node (ref "Q24") (pin "3") (pinfunction "C_3") (pintype "passive"))
    )
    (net (code "34") (name "/hang24") (class "Default")
      (node (ref "13") (pin "0") (pinfunction "0_0") (pintype "input"))
      (node (ref "14") (pin "0") (pinfunction "0_0") (pintype "input"))
      (node (ref "15") (pin "0") (pinfunction "0_0") (pintype "input"))
      (node (ref "16") (pin "0") (pinfunction "0_0") (pintype "input"))
      (node (ref "Q25") (pin "3") (pinfunction "C_3") (pintype "passive"))
    )
    (net (code "35") (name "/hang25") (class "Default")
      (node (ref "13") (pin "1") (pinfunction "1_1") (pintype "input"))
      (node (ref "14") (pin "1") (pinfunction "1_1") (pintype "input"))
      (node (ref "15") (pin "1") (pinfunction "1_1") (pintype "input"))
      (node (ref "16") (pin "1") (pinfunction "1_1") (pintype "input"))
      (node (ref "Q26") (pin "3") (pinfunction "C_3") (pintype "passive"))
    )
    (net (code "36") (name "/hang26") (class "Default")
      (node (ref "13") (pin "2") (pinfunction "2_2") (pintype "input"))
      (node (ref "14") (pin "2") (pinfunction "2_2") (pintype "input"))
      (node (ref "15") (pin "2") (pinfunction "2_2") (pintype "input"))
      (node (ref "16") (pin "2") (pinfunction "2_2") (pintype "input"))
      (node (ref "Q27") (pin "3") (pinfunction "C_3") (pintype "passive"))
    )
    (net (code "37") (name "/hang27") (class "Default")
      (node (ref "13") (pin "3") (pinfunction "3_3") (pintype "input"))
      (node (ref "14") (pin "3") (pinfunction "3_3") (pintype "input"))
      (node (ref "15") (pin "3") (pinfunction "3_3") (pintype "input"))
      (node (ref "16") (pin "3") (pinfunction "3_3") (pintype "input"))
      (node (ref "Q28") (pin "3") (pinfunction "C_3") (pintype "passive"))
    )
    (net (code "38") (name "/hang28") (class "Default")
      (node (ref "13") (pin "4") (pinfunction "4_4") (pintype "input"))
      (node (ref "14") (pin "4") (pinfunction "4_4") (pintype "input"))
      (node (ref "15") (pin "4") (pinfunction "4_4") (pintype "input"))
      (node (ref "16") (pin "4") (pinfunction "4_4") (pintype "input"))
      (node (ref "Q29") (pin "3") (pinfunction "C_3") (pintype "passive"))
    )
    (net (code "39") (name "/hang29") (class "Default")
      (node (ref "13") (pin "5") (pinfunction "5_5") (pintype "input"))
      (node (ref "14") (pin "5") (pinfunction "5_5") (pintype "input"))
      (node (ref "15") (pin "5") (pinfunction "5_5") (pintype "input"))
      (node (ref "16") (pin "5") (pinfunction "5_5") (pintype "input"))
      (node (ref "Q30") (pin "3") (pinfunction "C_3") (pintype "passive"))
    )
    (net (code "40") (name "/hang30") (class "Default")
      (node (ref "13") (pin "6") (pinfunction "6_6") (pintype "input"))
      (node (ref "14") (pin "6") (pinfunction "6_6") (pintype "input"))
      (node (ref "15") (pin "6") (pinfunction "6_6") (pintype "input"))
      (node (ref "16") (pin "6") (pinfunction "6_6") (pintype "input"))
      (node (ref "Q31") (pin "3") (pinfunction "C_3") (pintype "passive"))
    )
    (net (code "41") (name "/hang31") (class "Default")
      (node (ref "13") (pin "7") (pinfunction "7_7") (pintype "input"))
      (node (ref "14") (pin "7") (pinfunction "7_7") (pintype "input"))
      (node (ref "15") (pin "7") (pinfunction "7_7") (pintype "input"))
      (node (ref "16") (pin "7") (pinfunction "7_7") (pintype "input"))
      (node (ref "Q32") (pin "3") (pinfunction "C_3") (pintype "passive"))
    )
    (net (code "42") (name "/lie0") (class "Default")
      (node (ref "1") (pin "8") (pinfunction "8_8") (pintype "input"))
      (node (ref "13") (pin "8") (pinfunction "8_8") (pintype "input"))
      (node (ref "5") (pin "8") (pinfunction "8_8") (pintype "input"))
      (node (ref "9") (pin "8") (pinfunction "8_8") (pintype "input"))
      (node (ref "U1") (pin "15") (pinfunction "QA_15") (pintype "tri_state"))
    )
    (net (code "43") (name "/lie1") (class "Default")
      (node (ref "1") (pin "9") (pinfunction "9_9") (pintype "input"))
      (node (ref "13") (pin "9") (pinfunction "9_9") (pintype "input"))
      (node (ref "5") (pin "9") (pinfunction "9_9") (pintype "input"))
      (node (ref "9") (pin "9") (pinfunction "9_9") (pintype "input"))
      (node (ref "U1") (pin "1") (pinfunction "QB_1") (pintype "tri_state"))
    )
    (net (code "44") (name "/lie2") (class "Default")
      (node (ref "1") (pin "10") (pinfunction "10_10") (pintype "input"))
      (node (ref "13") (pin "10") (pinfunction "10_10") (pintype "input"))
      (node (ref "5") (pin "10") (pinfunction "10_10") (pintype "input"))
      (node (ref "9") (pin "10") (pinfunction "10_10") (pintype "input"))
      (node (ref "U1") (pin "2") (pinfunction "QC_2") (pintype "tri_state"))
    )
    (net (code "45") (name "/lie3") (class "Default")
      (node (ref "1") (pin "11") (pinfunction "11_11") (pintype "input"))
      (node (ref "13") (pin "11") (pinfunction "11_11") (pintype "input"))
      (node (ref "5") (pin "11") (pinfunction "11_11") (pintype "input"))
      (node (ref "9") (pin "11") (pinfunction "11_11") (pintype "input"))
      (node (ref "U1") (pin "3") (pinfunction "QD_3") (pintype "tri_state"))
    )
    (net (code "46") (name "/lie4") (class "Default")
      (node (ref "1") (pin "12") (pinfunction "12_12") (pintype "input"))
      (node (ref "13") (pin "12") (pinfunction "12_12") (pintype "input"))
      (node (ref "5") (pin "12") (pinfunction "12_12") (pintype "input"))
      (node (ref "9") (pin "12") (pinfunction "12_12") (pintype "input"))
      (node (ref "U1") (pin "4") (pinfunction "QE_4") (pintype "tri_state"))
    )
    (net (code "47") (name "/lie5") (class "Default")
      (node (ref "1") (pin "13") (pinfunction "13_13") (pintype "input"))
      (node (ref "13") (pin "13") (pinfunction "13_13") (pintype "input"))
      (node (ref "5") (pin "13") (pinfunction "13_13") (pintype "input"))
      (node (ref "9") (pin "13") (pinfunction "13_13") (pintype "input"))
      (node (ref "U1") (pin "5") (pinfunction "QF_5") (pintype "tri_state"))
    )
    (net (code "48") (name "/lie6") (class "Default")
      (node (ref "1") (pin "14") (pinfunction "14_14") (pintype "input"))
      (node (ref "13") (pin "14") (pinfunction "14_14") (pintype "input"))
      (node (ref "5") (pin "14") (pinfunction "14_14") (pintype "input"))
      (node (ref "9") (pin "14") (pinfunction "14_14") (pintype "input"))
      (node (ref "U1") (pin "6") (pinfunction "QG_6") (pintype "tri_state"))
    )
    (net (code "49") (name "/lie7") (class "Default")
      (node (ref "1") (pin "15") (pinfunction "15_15") (pintype "input"))
      (node (ref "13") (pin "15") (pinfunction "15_15") (pintype "input"))
      (node (ref "5") (pin "15") (pinfunction "15_15") (pintype "input"))
      (node (ref "9") (pin "15") (pinfunction "15_15") (pintype "input"))
      (node (ref "U1") (pin "7") (pinfunction "QH_7") (pintype "tri_state"))
    )
    (net (code "50") (name "/lie8") (class "Default")
      (node (ref "10") (pin "8") (pinfunction "8_8") (pintype "input"))
      (node (ref "14") (pin "8") (pinfunction "8_8") (pintype "input"))
      (node (ref "2") (pin "8") (pinfunction "8_8") (pintype "input"))
      (node (ref "6") (pin "8") (pinfunction "8_8") (pintype "input"))
      (node (ref "U2") (pin "15") (pinfunction "QA_15") (pintype "tri_state"))
    )
    (net (code "51") (name "/lie9") (class "Default")
      (node (ref "10") (pin "9") (pinfunction "9_9") (pintype "input"))
      (node (ref "14") (pin "9") (pinfunction "9_9") (pintype "input"))
      (node (ref "2") (pin "9") (pinfunction "9_9") (pintype "input"))
      (node (ref "6") (pin "9") (pinfunction "9_9") (pintype "input"))
      (node (ref "U2") (pin "1") (pinfunction "QB_1") (pintype "tri_state"))
    )
    (net (code "52") (name "/lie10") (class "Default")
      (node (ref "10") (pin "10") (pinfunction "10_10") (pintype "input"))
      (node (ref "14") (pin "10") (pinfunction "10_10") (pintype "input"))
      (node (ref "2") (pin "10") (pinfunction "10_10") (pintype "input"))
      (node (ref "6") (pin "10") (pinfunction "10_10") (pintype "input"))
      (node (ref "U2") (pin "2") (pinfunction "QC_2") (pintype "tri_state"))
    )
    (net (code "53") (name "/lie11") (class "Default")
      (node (ref "10") (pin "11") (pinfunction "11_11") (pintype "input"))
      (node (ref "14") (pin "11") (pinfunction "11_11") (pintype "input"))
      (node (ref "2") (pin "11") (pinfunction "11_11") (pintype "input"))
      (node (ref "6") (pin "11") (pinfunction "11_11") (pintype "input"))
      (node (ref "U2") (pin "3") (pinfunction "QD_3") (pintype "tri_state"))
    )
    (net (code "54") (name "/lie12") (class "Default")
      (node (ref "10") (pin "12") (pinfunction "12_12") (pintype "input"))
      (node (ref "14") (pin "12") (pinfunction "12_12") (pintype "input"))
      (node (ref "2") (pin "12") (pinfunction "12_12") (pintype "input"))
      (node (ref "6") (pin "12") (pinfunction "12_12") (pintype "input"))
      (node (ref "U2") (pin "4") (pinfunction "QE_4") (pintype "tri_state"))
    )
    (net (code "55") (name "/lie13") (class "Default")
      (node (ref "10") (pin "13") (pinfunction "13_13") (pintype "input"))
      (node (ref "14") (pin "13") (pinfunction "13_13") (pintype "input"))
      (node (ref "2") (pin "13") (pinfunction "13_13") (pintype "input"))
      (node (ref "6") (pin "13") (pinfunction "13_13") (pintype "input"))
      (node (ref "U2") (pin "5") (pinfunction "QF_5") (pintype "tri_state"))
    )
    (net (code "56") (name "/lie14") (class "Default")
      (node (ref "10") (pin "14") (pinfunction "14_14") (pintype "input"))
      (node (ref "14") (pin "14") (pinfunction "14_14") (pintype "input"))
      (node (ref "2") (pin "14") (pinfunction "14_14") (pintype "input"))
      (node (ref "6") (pin "14") (pinfunction "14_14") (pintype "input"))
      (node (ref "U2") (pin "6") (pinfunction "QG_6") (pintype "tri_state"))
    )
    (net (code "57") (name "/lie15") (class "Default")
      (node (ref "10") (pin "15") (pinfunction "15_15") (pintype "input"))
      (node (ref "14") (pin "15") (pinfunction "15_15") (pintype "input"))
      (node (ref "2") (pin "15") (pinfunction "15_15") (pintype "input"))
      (node (ref "6") (pin "15") (pinfunction "15_15") (pintype "input"))
      (node (ref "U2") (pin "7") (pinfunction "QH_7") (pintype "tri_state"))
    )
    (net (code "58") (name "/lie16") (class "Default")
      (node (ref "11") (pin "8") (pinfunction "8_8") (pintype "input"))
      (node (ref "15") (pin "8") (pinfunction "8_8") (pintype "input"))
      (node (ref "3") (pin "8") (pinfunction "8_8") (pintype "input"))
      (node (ref "7") (pin "8") (pinfunction "8_8") (pintype "input"))
      (node (ref "U3") (pin "15") (pinfunction "QA_15") (pintype "tri_state"))
    )
    (net (code "59") (name "/lie17") (class "Default")
      (node (ref "11") (pin "9") (pinfunction "9_9") (pintype "input"))
      (node (ref "15") (pin "9") (pinfunction "9_9") (pintype "input"))
      (node (ref "3") (pin "9") (pinfunction "9_9") (pintype "input"))
      (node (ref "7") (pin "9") (pinfunction "9_9") (pintype "input"))
      (node (ref "U3") (pin "1") (pinfunction "QB_1") (pintype "tri_state"))
    )
    (net (code "60") (name "/lie18") (class "Default")
      (node (ref "11") (pin "10") (pinfunction "10_10") (pintype "input"))
      (node (ref "15") (pin "10") (pinfunction "10_10") (pintype "input"))
      (node (ref "3") (pin "10") (pinfunction "10_10") (pintype "input"))
      (node (ref "7") (pin "10") (pinfunction "10_10") (pintype "input"))
      (node (ref "U3") (pin "2") (pinfunction "QC_2") (pintype "tri_state"))
    )
    (net (code "61") (name "/lie19") (class "Default")
      (node (ref "11") (pin "11") (pinfunction "11_11") (pintype "input"))
      (node (ref "15") (pin "11") (pinfunction "11_11") (pintype "input"))
      (node (ref "3") (pin "11") (pinfunction "11_11") (pintype "input"))
      (node (ref "7") (pin "11") (pinfunction "11_11") (pintype "input"))
      (node (ref "U3") (pin "3") (pinfunction "QD_3") (pintype "tri_state"))
    )
    (net (code "62") (name "/lie20") (class "Default")
      (node (ref "11") (pin "12") (pinfunction "12_12") (pintype "input"))
      (node (ref "15") (pin "12") (pinfunction "12_12") (pintype "input"))
      (node (ref "3") (pin "12") (pinfunction "12_12") (pintype "input"))
      (node (ref "7") (pin "12") (pinfunction "12_12") (pintype "input"))
      (node (ref "U3") (pin "4") (pinfunction "QE_4") (pintype "tri_state"))
    )
    (net (code "63") (name "/lie21") (class "Default")
      (node (ref "11") (pin "13") (pinfunction "13_13") (pintype "input"))
      (node (ref "15") (pin "13") (pinfunction "13_13") (pintype "input"))
      (node (ref "3") (pin "13") (pinfunction "13_13") (pintype "input"))
      (node (ref "7") (pin "13") (pinfunction "13_13") (pintype "input"))
      (node (ref "U3") (pin "5") (pinfunction "QF_5") (pintype "tri_state"))
    )
    (net (code "64") (name "/lie22") (class "Default")
      (node (ref "11") (pin "14") (pinfunction "14_14") (pintype "input"))
      (node (ref "15") (pin "14") (pinfunction "14_14") (pintype "input"))
      (node (ref "3") (pin "14") (pinfunction "14_14") (pintype "input"))
      (node (ref "7") (pin "14") (pinfunction "14_14") (pintype "input"))
      (node (ref "U3") (pin "6") (pinfunction "QG_6") (pintype "tri_state"))
    )
    (net (code "65") (name "/lie23") (class "Default")
      (node (ref "11") (pin "15") (pinfunction "15_15") (pintype "input"))
      (node (ref "15") (pin "15") (pinfunction "15_15") (pintype "input"))
      (node (ref "3") (pin "15") (pinfunction "15_15") (pintype "input"))
      (node (ref "7") (pin "15") (pinfunction "15_15") (pintype "input"))
      (node (ref "U3") (pin "7") (pinfunction "QH_7") (pintype "tri_state"))
    )
    (net (code "66") (name "/lie24") (class "Default")
      (node (ref "12") (pin "8") (pinfunction "8_8") (pintype "input"))
      (node (ref "16") (pin "8") (pinfunction "8_8") (pintype "input"))
      (node (ref "4") (pin "8") (pinfunction "8_8") (pintype "input"))
      (node (ref "8") (pin "8") (pinfunction "8_8") (pintype "input"))
      (node (ref "U4") (pin "15") (pinfunction "QA_15") (pintype "tri_state"))
    )
    (net (code "67") (name "/lie25") (class "Default")
      (node (ref "12") (pin "9") (pinfunction "9_9") (pintype "input"))
      (node (ref "16") (pin "9") (pinfunction "9_9") (pintype "input"))
      (node (ref "4") (pin "9") (pinfunction "9_9") (pintype "input"))
      (node (ref "8") (pin "9") (pinfunction "9_9") (pintype "input"))
      (node (ref "U4") (pin "1") (pinfunction "QB_1") (pintype "tri_state"))
    )
    (net (code "68") (name "/lie26") (class "Default")
      (node (ref "12") (pin "10") (pinfunction "10_10") (pintype "input"))
      (node (ref "16") (pin "10") (pinfunction "10_10") (pintype "input"))
      (node (ref "4") (pin "10") (pinfunction "10_10") (pintype "input"))
      (node (ref "8") (pin "10") (pinfunction "10_10") (pintype "input"))
      (node (ref "U4") (pin "2") (pinfunction "QC_2") (pintype "tri_state"))
    )
    (net (code "69") (name "/lie27") (class "Default")
      (node (ref "12") (pin "11") (pinfunction "11_11") (pintype "input"))
      (node (ref "16") (pin "11") (pinfunction "11_11") (pintype "input"))
      (node (ref "4") (pin "11") (pinfunction "11_11") (pintype "input"))
      (node (ref "8") (pin "11") (pinfunction "11_11") (pintype "input"))
      (node (ref "U4") (pin "3") (pinfunction "QD_3") (pintype "tri_state"))
    )
    (net (code "70") (name "/lie28") (class "Default")
      (node (ref "12") (pin "12") (pinfunction "12_12") (pintype "input"))
      (node (ref "16") (pin "12") (pinfunction "12_12") (pintype "input"))
      (node (ref "4") (pin "12") (pinfunction "12_12") (pintype "input"))
      (node (ref "8") (pin "12") (pinfunction "12_12") (pintype "input"))
      (node (ref "U4") (pin "4") (pinfunction "QE_4") (pintype "tri_state"))
    )
    (net (code "71") (name "/lie29") (class "Default")
      (node (ref "12") (pin "13") (pinfunction "13_13") (pintype "input"))
      (node (ref "16") (pin "13") (pinfunction "13_13") (pintype "input"))
      (node (ref "4") (pin "13") (pinfunction "13_13") (pintype "input"))
      (node (ref "8") (pin "13") (pinfunction "13_13") (pintype "input"))
      (node (ref "U4") (pin "5") (pinfunction "QF_5") (pintype "tri_state"))
    )
    (net (code "72") (name "/lie30") (class "Default")
      (node (ref "12") (pin "14") (pinfunction "14_14") (pintype "input"))
      (node (ref "16") (pin "14") (pinfunction "14_14") (pintype "input"))
      (node (ref "4") (pin "14") (pinfunction "14_14") (pintype "input"))
      (node (ref "8") (pin "14") (pinfunction "14_14") (pintype "input"))
      (node (ref "U4") (pin "6") (pinfunction "QG_6") (pintype "tri_state"))
    )
    (net (code "73") (name "/lie31") (class "Default")
      (node (ref "12") (pin "15") (pinfunction "15_15") (pintype "input"))
      (node (ref "16") (pin "15") (pinfunction "15_15") (pintype "input"))
      (node (ref "4") (pin "15") (pinfunction "15_15") (pintype "input"))
      (node (ref "8") (pin "15") (pinfunction "15_15") (pintype "input"))
      (node (ref "U4") (pin "7") (pinfunction "QH_7") (pintype "tri_state"))
    )
    (net (code "74") (name "5V") (class "Default")
      (node (ref "P2") (pin "1") (pinfunction "1_1") (pintype "passive"))
      (node (ref "P2") (pin "2") (pinfunction "2_2") (pintype "passive"))
      (node (ref "P2") (pin "3") (pinfunction "3_3") (pintype "passive"))
      (node (ref "P2") (pin "4") (pinfunction "4_4") (pintype "passive"))
      (node (ref "Q1") (pin "1") (pinfunction "E_1") (pintype "passive"))
      (node (ref "Q10") (pin "1") (pinfunction "E_1") (pintype "passive"))
      (node (ref "Q11") (pin "1") (pinfunction "E_1") (pintype "passive"))
      (node (ref "Q12") (pin "1") (pinfunction "E_1") (pintype "passive"))
      (node (ref "Q13") (pin "1") (pinfunction "E_1") (pintype "passive"))
      (node (ref "Q14") (pin "1") (pinfunction "E_1") (pintype "passive"))
      (node (ref "Q15") (pin "1") (pinfunction "E_1") (pintype "passive"))
      (node (ref "Q16") (pin "1") (pinfunction "E_1") (pintype "passive"))
      (node (ref "Q17") (pin "1") (pinfunction "E_1") (pintype "passive"))
      (node (ref "Q18") (pin "1") (pinfunction "E_1") (pintype "passive"))
      (node (ref "Q19") (pin "1") (pinfunction "E_1") (pintype "passive"))
      (node (ref "Q2") (pin "1") (pinfunction "E_1") (pintype "passive"))
      (node (ref "Q20") (pin "1") (pinfunction "E_1") (pintype "passive"))
      (node (ref "Q21") (pin "1") (pinfunction "E_1") (pintype "passive"))
      (node (ref "Q22") (pin "1") (pinfunction "E_1") (pintype "passive"))
      (node (ref "Q23") (pin "1") (pinfunction "E_1") (pintype "passive"))
      (node (ref "Q24") (pin "1") (pinfunction "E_1") (pintype "passive"))
      (node (ref "Q25") (pin "1") (pinfunction "E_1") (pintype "passive"))
      (node (ref "Q26") (pin "1") (pinfunction "E_1") (pintype "passive"))
      (node (ref "Q27") (pin "1") (pinfunction "E_1") (pintype "passive"))
      (node (ref "Q28") (pin "1") (pinfunction "E_1") (pintype "passive"))
      (node (ref "Q29") (pin "1") (pinfunction "E_1") (pintype "passive"))
      (node (ref "Q3") (pin "1") (pinfunction "E_1") (pintype "passive"))
      (node (ref "Q30") (pin "1") (pinfunction "E_1") (pintype "passive"))
      (node (ref "Q31") (pin "1") (pinfunction "E_1") (pintype "passive"))
      (node (ref "Q32") (pin "1") (pinfunction "E_1") (pintype "passive"))
      (node (ref "Q4") (pin "1") (pinfunction "E_1") (pintype "passive"))
      (node (ref "Q5") (pin "1") (pinfunction "E_1") (pintype "passive"))
      (node (ref "Q6") (pin "1") (pinfunction "E_1") (pintype "passive"))
      (node (ref "Q7") (pin "1") (pinfunction "E_1") (pintype "passive"))
      (node (ref "Q8") (pin "1") (pinfunction "E_1") (pintype "passive"))
      (node (ref "Q9") (pin "1") (pinfunction "E_1") (pintype "passive"))
      (node (ref "U1") (pin "10") (pinfunction "~{RST}_10") (pintype "input"))
      (node (ref "U1") (pin "16") (pinfunction "VDD_16") (pintype "power_in"))
      (node (ref "U2") (pin "10") (pinfunction "~{RST}_10") (pintype "input"))
      (node (ref "U2") (pin "16") (pinfunction "VDD_16") (pintype "power_in"))
      (node (ref "U3") (pin "10") (pinfunction "~{RST}_10") (pintype "input"))
      (node (ref "U3") (pin "16") (pinfunction "VDD_16") (pintype "power_in"))
      (node (ref "U4") (pin "10") (pinfunction "~{RST}_10") (pintype "input"))
      (node (ref "U4") (pin "16") (pinfunction "VDD_16") (pintype "power_in"))
      (node (ref "U5") (pin "16") (pinfunction "VCC_16") (pintype "power_in"))
      (node (ref "U5") (pin "6") (pinfunction "OE1_6") (pintype "input"))
      (node (ref "U6") (pin "16") (pinfunction "VCC_16") (pintype "power_in"))
      (node (ref "U7") (pin "16") (pinfunction "VCC_16") (pintype "power_in"))
      (node (ref "U7") (pin "6") (pinfunction "OE1_6") (pintype "input"))
      (node (ref "U8") (pin "16") (pinfunction "VCC_16") (pintype "power_in"))
    )
    (net (code "75") (name "GND") (class "Default")
      (node (ref "P2") (pin "5") (pinfunction "5_5") (pintype "passive"))
      (node (ref "P2") (pin "6") (pinfunction "6_6") (pintype "passive"))
      (node (ref "P2") (pin "7") (pinfunction "7_7") (pintype "passive"))
      (node (ref "P2") (pin "8") (pinfunction "8_8") (pintype "passive"))
      (node (ref "U1") (pin "13") (pinfunction "~{OE}_13") (pintype "input"))
      (node (ref "U1") (pin "8") (pinfunction "GND_8") (pintype "power_in"))
      (node (ref "U2") (pin "13") (pinfunction "~{OE}_13") (pintype "input"))
      (node (ref "U2") (pin "8") (pinfunction "GND_8") (pintype "power_in"))
      (node (ref "U3") (pin "13") (pinfunction "~{OE}_13") (pintype "input"))
      (node (ref "U3") (pin "8") (pinfunction "GND_8") (pintype "power_in"))
      (node (ref "U4") (pin "13") (pinfunction "~{OE}_13") (pintype "input"))
      (node (ref "U4") (pin "8") (pinfunction "GND_8") (pintype "power_in"))
      (node (ref "U5") (pin "8") (pinfunction "GND_8") (pintype "power_in"))
      (node (ref "U6") (pin "8") (pinfunction "GND_8") (pintype "power_in"))
      (node (ref "U7") (pin "8") (pinfunction "GND_8") (pintype "power_in"))
      (node (ref "U8") (pin "8") (pinfunction "GND_8") (pintype "power_in"))
    )
    (net (code "76") (name "Net-(Q1-B)") (class "Default")
      (node (ref "Q1") (pin "2") (pinfunction "B_2") (pintype "passive"))
      (node (ref "R1") (pin "2") (pinfunction "2_2") (pintype "passive"))
    )
    (net (code "77") (name "Net-(Q2-B)") (class "Default")
      (node (ref "Q2") (pin "2") (pinfunction "B_2") (pintype "passive"))
      (node (ref "R2") (pin "2") (pinfunction "2_2") (pintype "passive"))
    )
    (net (code "78") (name "Net-(Q3-B)") (class "Default")
      (node (ref "Q3") (pin "2") (pinfunction "B_2") (pintype "passive"))
      (node (ref "R3") (pin "2") (pinfunction "2_2") (pintype "passive"))
    )
    (net (code "79") (name "Net-(Q4-B)") (class "Default")
      (node (ref "Q4") (pin "2") (pinfunction "B_2") (pintype "passive"))
      (node (ref "R4") (pin "2") (pinfunction "2_2") (pintype "passive"))
    )
    (net (code "80") (name "Net-(Q5-B)") (class "Default")
      (node (ref "Q5") (pin "2") (pinfunction "B_2") (pintype "passive"))
      (node (ref "R5") (pin "2") (pinfunction "2_2") (pintype "passive"))
    )
    (net (code "81") (name "Net-(Q6-B)") (class "Default")
      (node (ref "Q6") (pin "2") (pinfunction "B_2") (pintype "passive"))
      (node (ref "R6") (pin "2") (pinfunction "2_2") (pintype "passive"))
    )
    (net (code "82") (name "Net-(Q7-B)") (class "Default")
      (node (ref "Q7") (pin "2") (pinfunction "B_2") (pintype "passive"))
      (node (ref "R7") (pin "2") (pinfunction "2_2") (pintype "passive"))
    )
    (net (code "83") (name "Net-(Q8-B)") (class "Default")
      (node (ref "Q8") (pin "2") (pinfunction "B_2") (pintype "passive"))
      (node (ref "R8") (pin "2") (pinfunction "2_2") (pintype "passive"))
    )
    (net (code "84") (name "Net-(Q9-B)") (class "Default")
      (node (ref "Q9") (pin "2") (pinfunction "B_2") (pintype "passive"))
      (node (ref "R9") (pin "2") (pinfunction "2_2") (pintype "passive"))
    )
    (net (code "85") (name "Net-(Q10-B)") (class "Default")
      (node (ref "Q10") (pin "2") (pinfunction "B_2") (pintype "passive"))
      (node (ref "R10") (pin "2") (pinfunction "2_2") (pintype "passive"))
    )
    (net (code "86") (name "Net-(Q11-B)") (class "Default")
      (node (ref "Q11") (pin "2") (pinfunction "B_2") (pintype "passive"))
      (node (ref "R11") (pin "2") (pinfunction "2_2") (pintype "passive"))
    )
    (net (code "87") (name "Net-(Q12-B)") (class "Default")
      (node (ref "Q12") (pin "2") (pinfunction "B_2") (pintype "passive"))
      (node (ref "R12") (pin "2") (pinfunction "2_2") (pintype "passive"))
    )
    (net (code "88") (name "Net-(Q13-B)") (class "Default")
      (node (ref "Q13") (pin "2") (pinfunction "B_2") (pintype "passive"))
      (node (ref "R13") (pin "2") (pinfunction "2_2") (pintype "passive"))
    )
    (net (code "89") (name "Net-(Q14-B)") (class "Default")
      (node (ref "Q14") (pin "2") (pinfunction "B_2") (pintype "passive"))
      (node (ref "R14") (pin "2") (pinfunction "2_2") (pintype "passive"))
    )
    (net (code "90") (name "Net-(Q15-B)") (class "Default")
      (node (ref "Q15") (pin "2") (pinfunction "B_2") (pintype "passive"))
      (node (ref "R15") (pin "2") (pinfunction "2_2") (pintype "passive"))
    )
    (net (code "91") (name "Net-(Q16-B)") (class "Default")
      (node (ref "Q16") (pin "2") (pinfunction "B_2") (pintype "passive"))
      (node (ref "R16") (pin "2") (pinfunction "2_2") (pintype "passive"))
    )
    (net (code "92") (name "Net-(Q17-B)") (class "Default")
      (node (ref "Q17") (pin "2") (pinfunction "B_2") (pintype "passive"))
      (node (ref "R17") (pin "2") (pinfunction "2_2") (pintype "passive"))
    )
    (net (code "93") (name "Net-(Q18-B)") (class "Default")
      (node (ref "Q18") (pin "2") (pinfunction "B_2") (pintype "passive"))
      (node (ref "R18") (pin "2") (pinfunction "2_2") (pintype "passive"))
    )
    (net (code "94") (name "Net-(Q19-B)") (class "Default")
      (node (ref "Q19") (pin "2") (pinfunction "B_2") (pintype "passive"))
      (node (ref "R19") (pin "2") (pinfunction "2_2") (pintype "passive"))
    )
    (net (code "95") (name "Net-(Q20-B)") (class "Default")
      (node (ref "Q20") (pin "2") (pinfunction "B_2") (pintype "passive"))
      (node (ref "R20") (pin "2") (pinfunction "2_2") (pintype "passive"))
    )
    (net (code "96") (name "Net-(Q21-B)") (class "Default")
      (node (ref "Q21") (pin "2") (pinfunction "B_2") (pintype "passive"))
      (node (ref "R21") (pin "2") (pinfunction "2_2") (pintype "passive"))
    )
    (net (code "97") (name "Net-(Q22-B)") (class "Default")
      (node (ref "Q22") (pin "2") (pinfunction "B_2") (pintype "passive"))
      (node (ref "R22") (pin "2") (pinfunction "2_2") (pintype "passive"))
    )
    (net (code "98") (name "Net-(Q23-B)") (class "Default")
      (node (ref "Q23") (pin "2") (pinfunction "B_2") (pintype "passive"))
      (node (ref "R23") (pin "2") (pinfunction "2_2") (pintype "passive"))
    )
    (net (code "99") (name "Net-(Q24-B)") (class "Default")
      (node (ref "Q24") (pin "2") (pinfunction "B_2") (pintype "passive"))
      (node (ref "R24") (pin "2") (pinfunction "2_2") (pintype "passive"))
    )
    (net (code "100") (name "Net-(Q25-B)") (class "Default")
      (node (ref "Q25") (pin "2") (pinfunction "B_2") (pintype "passive"))
      (node (ref "R25") (pin "2") (pinfunction "2_2") (pintype "passive"))
    )
    (net (code "101") (name "Net-(Q26-B)") (class "Default")
      (node (ref "Q26") (pin "2") (pinfunction "B_2") (pintype "passive"))
      (node (ref "R26") (pin "2") (pinfunction "2_2") (pintype "passive"))
    )
    (net (code "102") (name "Net-(Q27-B)") (class "Default")
      (node (ref "Q27") (pin "2") (pinfunction "B_2") (pintype "passive"))
      (node (ref "R27") (pin "2") (pinfunction "2_2") (pintype "passive"))
    )
    (net (code "103") (name "Net-(Q28-B)") (class "Default")
      (node (ref "Q28") (pin "2") (pinfunction "B_2") (pintype "passive"))
      (node (ref "R28") (pin "2") (pinfunction "2_2") (pintype "passive"))
    )
    (net (code "104") (name "Net-(Q29-B)") (class "Default")
      (node (ref "Q29") (pin "2") (pinfunction "B_2") (pintype "passive"))
      (node (ref "R29") (pin "2") (pinfunction "2_2") (pintype "passive"))
    )
    (net (code "105") (name "Net-(Q30-B)") (class "Default")
      (node (ref "Q30") (pin "2") (pinfunction "B_2") (pintype "passive"))
      (node (ref "R30") (pin "2") (pinfunction "2_2") (pintype "passive"))
    )
    (net (code "106") (name "Net-(Q31-B)") (class "Default")
      (node (ref "Q31") (pin "2") (pinfunction "B_2") (pintype "passive"))
      (node (ref "R31") (pin "2") (pinfunction "2_2") (pintype "passive"))
    )
    (net (code "107") (name "Net-(Q32-B)") (class "Default")
      (node (ref "Q32") (pin "2") (pinfunction "B_2") (pintype "passive"))
      (node (ref "R32") (pin "2") (pinfunction "2_2") (pintype "passive"))
    )
    (net (code "108") (name "Net-(U1-SDO)") (class "Default")
      (node (ref "U1") (pin "9") (pinfunction "SDO_9") (pintype "output"))
      (node (ref "U2") (pin "14") (pinfunction "SDI_14") (pintype "input"))
    )
    (net (code "109") (name "Net-(U2-SDO)") (class "Default")
      (node (ref "U2") (pin "9") (pinfunction "SDO_9") (pintype "output"))
      (node (ref "U3") (pin "14") (pinfunction "SDI_14") (pintype "input"))
    )
    (net (code "110") (name "Net-(U3-SDO)") (class "Default")
      (node (ref "U3") (pin "9") (pinfunction "SDO_9") (pintype "output"))
      (node (ref "U4") (pin "14") (pinfunction "SDI_14") (pintype "input"))
    )
    (net (code "111") (name "Net-(U5-~{Y}0)") (class "Default")
      (node (ref "R1") (pin "1") (pinfunction "1_1") (pintype "passive"))
      (node (ref "U5") (pin "15") (pinfunction "~{Y}0_15") (pintype "output"))
    )
    (net (code "112") (name "Net-(U5-~{Y}1)") (class "Default")
      (node (ref "R2") (pin "1") (pinfunction "1_1") (pintype "passive"))
      (node (ref "U5") (pin "14") (pinfunction "~{Y}1_14") (pintype "output"))
    )
    (net (code "113") (name "Net-(U5-~{Y}2)") (class "Default")
      (node (ref "R3") (pin "1") (pinfunction "1_1") (pintype "passive"))
      (node (ref "U5") (pin "13") (pinfunction "~{Y}2_13") (pintype "output"))
    )
    (net (code "114") (name "Net-(U5-~{Y}3)") (class "Default")
      (node (ref "R4") (pin "1") (pinfunction "1_1") (pintype "passive"))
      (node (ref "U5") (pin "12") (pinfunction "~{Y}3_12") (pintype "output"))
    )
    (net (code "115") (name "Net-(U5-~{Y}4)") (class "Default")
      (node (ref "R5") (pin "1") (pinfunction "1_1") (pintype "passive"))
      (node (ref "U5") (pin "11") (pinfunction "~{Y}4_11") (pintype "output"))
    )
    (net (code "116") (name "Net-(U5-~{Y}5)") (class "Default")
      (node (ref "R6") (pin "1") (pinfunction "1_1") (pintype "passive"))
      (node (ref "U5") (pin "10") (pinfunction "~{Y}5_10") (pintype "output"))
    )
    (net (code "117") (name "Net-(U5-~{Y}6)") (class "Default")
      (node (ref "R7") (pin "1") (pinfunction "1_1") (pintype "passive"))
      (node (ref "U5") (pin "9") (pinfunction "~{Y}6_9") (pintype "output"))
    )
    (net (code "118") (name "Net-(U5-~{Y}7)") (class "Default")
      (node (ref "R8") (pin "1") (pinfunction "1_1") (pintype "passive"))
      (node (ref "U5") (pin "7") (pinfunction "~{Y}7_7") (pintype "output"))
    )
    (net (code "119") (name "Net-(U6-~{Y}0)") (class "Default")
      (node (ref "R9") (pin "1") (pinfunction "1_1") (pintype "passive"))
      (node (ref "U6") (pin "15") (pinfunction "~{Y}0_15") (pintype "output"))
    )
    (net (code "120") (name "Net-(U6-~{Y}1)") (class "Default")
      (node (ref "R10") (pin "1") (pinfunction "1_1") (pintype "passive"))
      (node (ref "U6") (pin "14") (pinfunction "~{Y}1_14") (pintype "output"))
    )
    (net (code "121") (name "Net-(U6-~{Y}2)") (class "Default")
      (node (ref "R11") (pin "1") (pinfunction "1_1") (pintype "passive"))
      (node (ref "U6") (pin "13") (pinfunction "~{Y}2_13") (pintype "output"))
    )
    (net (code "122") (name "Net-(U6-~{Y}3)") (class "Default")
      (node (ref "R12") (pin "1") (pinfunction "1_1") (pintype "passive"))
      (node (ref "U6") (pin "12") (pinfunction "~{Y}3_12") (pintype "output"))
    )
    (net (code "123") (name "Net-(U6-~{Y}4)") (class "Default")
      (node (ref "R13") (pin "1") (pinfunction "1_1") (pintype "passive"))
      (node (ref "U6") (pin "11") (pinfunction "~{Y}4_11") (pintype "output"))
    )
    (net (code "124") (name "Net-(U6-~{Y}5)") (class "Default")
      (node (ref "R14") (pin "1") (pinfunction "1_1") (pintype "passive"))
      (node (ref "U6") (pin "10") (pinfunction "~{Y}5_10") (pintype "output"))
    )
    (net (code "125") (name "Net-(U6-~{Y}6)") (class "Default")
      (node (ref "R15") (pin "1") (pinfunction "1_1") (pintype "passive"))
      (node (ref "U6") (pin "9") (pinfunction "~{Y}6_9") (pintype "output"))
    )
    (net (code "126") (name "Net-(U6-~{Y}7)") (class "Default")
      (node (ref "R16") (pin "1") (pinfunction "1_1") (pintype "passive"))
      (node (ref "U6") (pin "7") (pinfunction "~{Y}7_7") (pintype "output"))
    )
    (net (code "127") (name "Net-(U7-~{Y}0)") (class "Default")
      (node (ref "R17") (pin "1") (pinfunction "1_1") (pintype "passive"))
      (node (ref "U7") (pin "15") (pinfunction "~{Y}0_15") (pintype "output"))
    )
    (net (code "128") (name "Net-(U7-~{Y}1)") (class "Default")
      (node (ref "R18") (pin "1") (pinfunction "1_1") (pintype "passive"))
      (node (ref "U7") (pin "14") (pinfunction "~{Y}1_14") (pintype "output"))
    )
    (net (code "129") (name "Net-(U7-~{Y}2)") (class "Default")
      (node (ref "R19") (pin "1") (pinfunction "1_1") (pintype "passive"))
      (node (ref "U7") (pin "13") (pinfunction "~{Y}2_13") (pintype "output"))
    )
    (net (code "130") (name "Net-(U7-~{Y}3)") (class "Default")
      (node (ref "R20") (pin "1") (pinfunction "1_1") (pintype "passive"))
      (node (ref "U7") (pin "12") (pinfunction "~{Y}3_12") (pintype "output"))
    )
    (net (code "131") (name "Net-(U7-~{Y}4)") (class "Default")
      (node (ref "R21") (pin "1") (pinfunction "1_1") (pintype "passive"))
      (node (ref "U7") (pin "11") (pinfunction "~{Y}4_11") (pintype "output"))
    )
    (net (code "132") (name "Net-(U7-~{Y}5)") (class "Default")
      (node (ref "R22") (pin "1") (pinfunction "1_1") (pintype "passive"))
      (node (ref "U7") (pin "10") (pinfunction "~{Y}5_10") (pintype "output"))
    )
    (net (code "133") (name "Net-(U7-~{Y}6)") (class "Default")
      (node (ref "R23") (pin "1") (pinfunction "1_1") (pintype "passive"))
      (node (ref "U7") (pin "9") (pinfunction "~{Y}6_9") (pintype "output"))
    )
    (net (code "134") (name "Net-(U7-~{Y}7)") (class "Default")
      (node (ref "R24") (pin "1") (pinfunction "1_1") (pintype "passive"))
      (node (ref "U7") (pin "7") (pinfunction "~{Y}7_7") (pintype "output"))
    )
    (net (code "135") (name "Net-(U8-~{Y}0)") (class "Default")
      (node (ref "R25") (pin "1") (pinfunction "1_1") (pintype "passive"))
      (node (ref "U8") (pin "15") (pinfunction "~{Y}0_15") (pintype "output"))
    )
    (net (code "136") (name "Net-(U8-~{Y}1)") (class "Default")
      (node (ref "R26") (pin "1") (pinfunction "1_1") (pintype "passive"))
      (node (ref "U8") (pin "14") (pinfunction "~{Y}1_14") (pintype "output"))
    )
    (net (code "137") (name "Net-(U8-~{Y}2)") (class "Default")
      (node (ref "R27") (pin "1") (pinfunction "1_1") (pintype "passive"))
      (node (ref "U8") (pin "13") (pinfunction "~{Y}2_13") (pintype "output"))
    )
    (net (code "138") (name "Net-(U8-~{Y}3)") (class "Default")
      (node (ref "R28") (pin "1") (pinfunction "1_1") (pintype "passive"))
      (node (ref "U8") (pin "12") (pinfunction "~{Y}3_12") (pintype "output"))
    )
    (net (code "139") (name "Net-(U8-~{Y}4)") (class "Default")
      (node (ref "R29") (pin "1") (pinfunction "1_1") (pintype "passive"))
      (node (ref "U8") (pin "11") (pinfunction "~{Y}4_11") (pintype "output"))
    )
    (net (code "140") (name "Net-(U8-~{Y}5)") (class "Default")
      (node (ref "R30") (pin "1") (pinfunction "1_1") (pintype "passive"))
      (node (ref "U8") (pin "10") (pinfunction "~{Y}5_10") (pintype "output"))
    )
    (net (code "141") (name "Net-(U8-~{Y}6)") (class "Default")
      (node (ref "R31") (pin "1") (pinfunction "1_1") (pintype "passive"))
      (node (ref "U8") (pin "9") (pinfunction "~{Y}6_9") (pintype "output"))
    )
    (net (code "142") (name "Net-(U8-~{Y}7)") (class "Default")
      (node (ref "R32") (pin "1") (pinfunction "1_1") (pintype "passive"))
      (node (ref "U8") (pin "7") (pinfunction "~{Y}7_7") (pintype "output"))
    )
    (net (code "143") (name "unconnected-(U4-SDO-Pad9)") (class "Default")
      (node (ref "U4") (pin "9") (pinfunction "SDO_9") (pintype "output"))
    )
  )
)
